# ATmega328.net
KiCad netlist of a schematic drawn in EAGLE
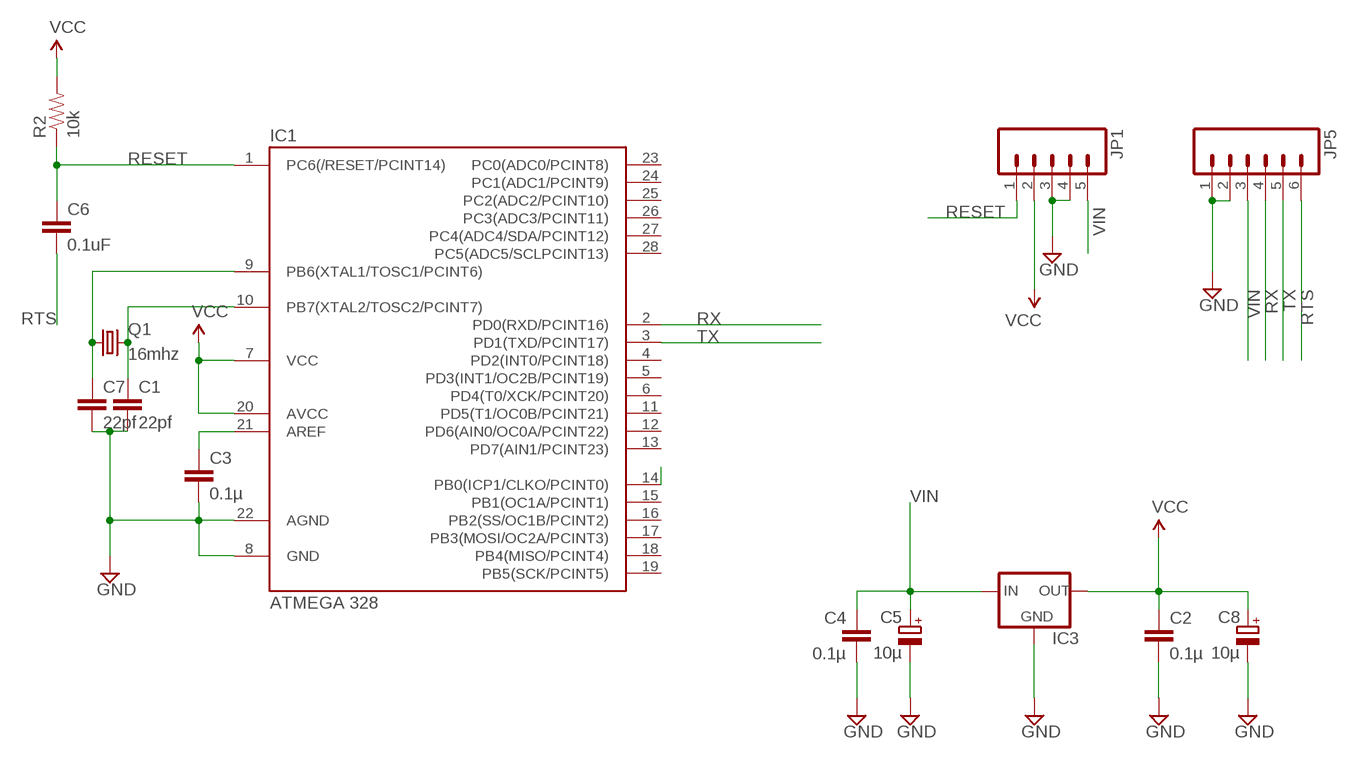
[diagram p0: schematic, sheet 1]

(export (version "E")
  (design (tool "Eeschema 10.0.6"))
  (components
    (comp (ref "C1")
      (value "22pf")
      (footprint "eagle-import:C025-024X044")
      (libsource (lib "eagle-import") (part "C-EU025-024X044"))
    )
    (comp (ref "C2")
      (value "0.1µ")
      (footprint "eagle-import:C025-024X044")
      (libsource (lib "eagle-import") (part "C-EU025-024X044"))
    )
    (comp (ref "C3")
      (value "0.1µ")
      (footprint "eagle-import:C025-024X044")
      (libsource (lib "eagle-import") (part "C-EU025-024X044"))
    )
    (comp (ref "C4")
      (value "0.1µ")
      (footprint "eagle-import:C025-024X044")
      (libsource (lib "eagle-import") (part "C-EU025-024X044"))
    )
    (comp (ref "C5")
      (value "10µ")
      (footprint "eagle-import:E1,8-4")
      (libsource (lib "eagle-import") (part "CPOL-EUE1.8-4"))
    )
    (comp (ref "C6")
      (value "0.1uF")
      (footprint "eagle-import:CAP-PTH-5MM")
      (libsource (lib "eagle-import") (part "CAPPTH1"))
    )
    (comp (ref "C7")
      (value "22pf")
      (footprint "eagle-import:C025-024X044")
      (libsource (lib "eagle-import") (part "C-EU025-024X044"))
    )
    (comp (ref "C8")
      (value "10µ")
      (footprint "eagle-import:E1,8-4")
      (libsource (lib "eagle-import") (part "CPOL-EUE1.8-4"))
    )
    (comp (ref "IC1")
      (value "ATMEGA 328")
      (footprint "eagle-import:DIL28-3")
      (libsource (lib "eagle-import") (part "ATMEGA48/88/168-PU"))
    )
    (comp (ref "IC3")
      (value "V_REG_78XXSIDE")
      (footprint "eagle-import:78XXL")
      (libsource (lib "eagle-import") (part "V_REG_78XXSIDE"))
    )
    (comp (ref "JP1")
      (value "M05PTH_LONGPADS")
      (footprint "eagle-import:1X05_LONGPADS")
      (libsource (lib "eagle-import") (part "M05PTH_LONGPADS"))
    )
    (comp (ref "JP5")
      (value "M06NO_SILK")
      (footprint "eagle-import:1X06_NO_SILK")
      (libsource (lib "eagle-import") (part "M06NO_SILK"))
    )
    (comp (ref "Q1")
      (value "16mhz")
      (footprint "eagle-import:HC49_S")
      (libsource (lib "eagle-import") (part "CRYSTALHC49S"))
    )
    (comp (ref "R2")
      (value "10k")
      (footprint "eagle-import:1_6W-RES")
      (libsource (lib "eagle-import") (part "RESISTORPTH-1/6W"))
    )
  )
  (nets
    (net (code "1") (name "/RESET") (class "Default")
      (node (ref "C6") (pin "1") (pinfunction "1_1") (pintype "passive"))
      (node (ref "IC1") (pin "1") (pinfunction "PC6(/RESET/PCINT14)_1") (pintype "bidirectional"))
      (node (ref "JP1") (pin "1") (pinfunction "1_1") (pintype "passive"))
      (node (ref "R2") (pin "1") (pinfunction "1_1") (pintype "passive"))
    )
    (net (code "2") (name "/RTS") (class "Default")
      (node (ref "C6") (pin "2") (pinfunction "2_2") (pintype "passive"))
      (node (ref "JP5") (pin "6") (pinfunction "6_6") (pintype "passive"))
    )
    (net (code "3") (name "/RX") (class "Default")
      (node (ref "IC1") (pin "2") (pinfunction "PD0(RXD/PCINT16)_2") (pintype "bidirectional"))
      (node (ref "JP5") (pin "4") (pinfunction "4_4") (pintype "passive"))
    )
    (net (code "4") (name "/TX") (class "Default")
      (node (ref "IC1") (pin "3") (pinfunction "PD1(TXD/PCINT17)_3") (pintype "bidirectional"))
      (node (ref "JP5") (pin "5") (pinfunction "5_5") (pintype "passive"))
    )
    (net (code "5") (name "/VIN") (class "Default")
      (node (ref "C4") (pin "1") (pinfunction "1_1") (pintype "passive"))
      (node (ref "C5") (pin "+") (pinfunction "+_+") (pintype "passive"))
      (node (ref "IC3") (pin "IN") (pinfunction "IN_IN") (pintype "input"))
      (node (ref "JP1") (pin "5") (pinfunction "5_5") (pintype "passive"))
      (node (ref "JP5") (pin "3") (pinfunction "3_3") (pintype "passive"))
    )
    (net (code "6") (name "GND") (class "Default")
      (node (ref "C1") (pin "2") (pinfunction "2_2") (pintype "passive"))
      (node (ref "C2") (pin "2") (pinfunction "2_2") (pintype "passive"))
      (node (ref "C3") (pin "2") (pinfunction "2_2") (pintype "passive"))
      (node (ref "C4") (pin "2") (pinfunction "2_2") (pintype "passive"))
      (node (ref "C5") (pin "-") (pinfunction "-_-") (pintype "passive"))
      (node (ref "C7") (pin "2") (pinfunction "2_2") (pintype "passive"))
      (node (ref "C8") (pin "-") (pinfunction "-_-") (pintype "passive"))
      (node (ref "IC1") (pin "22") (pinfunction "AGND_22") (pintype "power_in"))
      (node (ref "IC1") (pin "8") (pinfunction "GND_8") (pintype "power_in"))
      (node (ref "IC3") (pin "GND") (pinfunction "GND_GND") (pintype "input"))
      (node (ref "JP1") (pin "3") (pinfunction "3_3") (pintype "passive"))
      (node (ref "JP1") (pin "4") (pinfunction "4_4") (pintype "passive"))
      (node (ref "JP5") (pin "1") (pinfunction "1_1") (pintype "passive"))
      (node (ref "JP5") (pin "2") (pinfunction "2_2") (pintype "passive"))
    )
    (net (code "7") (name "Net-(IC1-AREF)") (class "Default")
      (node (ref "C3") (pin "1") (pinfunction "1_1") (pintype "passive"))
      (node (ref "IC1") (pin "21") (pinfunction "AREF_21") (pintype "passive"))
    )
    (net (code "8") (name "Net-(IC1-PB6(XTAL1{slash}TOSC1{slash}PCINT6))") (class "Default")
      (node (ref "C7") (pin "1") (pinfunction "1_1") (pintype "passive"))
      (node (ref "IC1") (pin "9") (pinfunction "PB6(XTAL1/TOSC1/PCINT6)_9") (pintype "bidirectional"))
      (node (ref "Q1") (pin "1") (pinfunction "1_1") (pintype "passive"))
    )
    (net (code "9") (name "Net-(IC1-PB7(XTAL2{slash}TOSC2{slash}PCINT7))") (class "Default")
      (node (ref "C1") (pin "1") (pinfunction "1_1") (pintype "passive"))
      (node (ref "IC1") (pin "10") (pinfunction "PB7(XTAL2/TOSC2/PCINT7)_10") (pintype "bidirectional"))
      (node (ref "Q1") (pin "2") (pinfunction "2_2") (pintype "passive"))
    )
    (net (code "10") (name "VCC") (class "Default")
      (node (ref "C2") (pin "1") (pinfunction "1_1") (pintype "passive"))
      (node (ref "C8") (pin "+") (pinfunction "+_+") (pintype "passive"))
      (node (ref "IC1") (pin "20") (pinfunction "AVCC_20") (pintype "passive"))
      (node (ref "IC1") (pin "7") (pinfunction "VCC_7") (pintype "power_in"))
      (node (ref "IC3") (pin "OUT") (pinfunction "OUT_OUT") (pintype "output"))
      (node (ref "JP1") (pin "2") (pinfunction "2_2") (pintype "passive"))
      (node (ref "R2") (pin "2") (pinfunction "2_2") (pintype "passive"))
    )
    (net (code "11") (name "unconnected-(IC1-PB0(ICP1{slash}CLKO{slash}PCINT0)-Pad14)") (class "Default")
      (node (ref "IC1") (pin "14") (pinfunction "PB0(ICP1/CLKO/PCINT0)_14") (pintype "bidirectional"))
    )
    (net (code "12") (name "unconnected-(IC1-PB1(OC1A{slash}PCINT1)-Pad15)") (class "Default")
      (node (ref "IC1") (pin "15") (pinfunction "PB1(OC1A/PCINT1)_15") (pintype "bidirectional"))
    )
    (net (code "13") (name "unconnected-(IC1-PB2(SS{slash}OC1B{slash}PCINT2)-Pad16)") (class "Default")
      (node (ref "IC1") (pin "16") (pinfunction "PB2(SS/OC1B/PCINT2)_16") (pintype "bidirectional"))
    )
    (net (code "14") (name "unconnected-(IC1-PB3(MOSI{slash}OC2A{slash}PCINT3)-Pad17)") (class "Default")
      (node (ref "IC1") (pin "17") (pinfunction "PB3(MOSI/OC2A/PCINT3)_17") (pintype "bidirectional"))
    )
    (net (code "15") (name "unconnected-(IC1-PB4(MISO{slash}PCINT4)-Pad18)") (class "Default")
      (node (ref "IC1") (pin "18") (pinfunction "PB4(MISO/PCINT4)_18") (pintype "bidirectional"))
    )
    (net (code "16") (name "unconnected-(IC1-PB5(SCK{slash}PCINT5)-Pad19)") (class "Default")
      (node (ref "IC1") (pin "19") (pinfunction "PB5(SCK/PCINT5)_19") (pintype "bidirectional"))
    )
    (net (code "17") (name "unconnected-(IC1-PC0(ADC0{slash}PCINT8)-Pad23)") (class "Default")
      (node (ref "IC1") (pin "23") (pinfunction "PC0(ADC0/PCINT8)_23") (pintype "bidirectional"))
    )
    (net (code "18") (name "unconnected-(IC1-PC1(ADC1{slash}PCINT9)-Pad24)") (class "Default")
      (node (ref "IC1") (pin "24") (pinfunction "PC1(ADC1/PCINT9)_24") (pintype "bidirectional"))
    )
    (net (code "19") (name "unconnected-(IC1-PC2(ADC2{slash}PCINT10)-Pad25)") (class "Default")
      (node (ref "IC1") (pin "25") (pinfunction "PC2(ADC2/PCINT10)_25") (pintype "bidirectional"))
    )
    (net (code "20") (name "unconnected-(IC1-PC3(ADC3{slash}PCINT11)-Pad26)") (class "Default")
      (node (ref "IC1") (pin "26") (pinfunction "PC3(ADC3/PCINT11)_26") (pintype "bidirectional"))
    )
    (net (code "21") (name "unconnected-(IC1-PC4(ADC4{slash}SDA{slash}PCINT12)-Pad27)") (class "Default")
      (node (ref "IC1") (pin "27") (pinfunction "PC4(ADC4/SDA/PCINT12)_27") (pintype "bidirectional"))
    )
    (net (code "22") (name "unconnected-(IC1-PC5(ADC5{slash}SCLPCINT13)-Pad28)") (class "Default")
      (node (ref "IC1") (pin "28") (pinfunction "PC5(ADC5/SCLPCINT13)_28") (pintype "bidirectional"))
    )
    (net (code "23") (name "unconnected-(IC1-PD2(INT0{slash}PCINT18)-Pad4)") (class "Default")
      (node (ref "IC1") (pin "4") (pinfunction "PD2(INT0/PCINT18)_4") (pintype "bidirectional"))
    )
    (net (code "24") (name "unconnected-(IC1-PD3(INT1{slash}OC2B{slash}PCINT19)-Pad5)") (class "Default")
      (node (ref "IC1") (pin "5") (pinfunction "PD3(INT1/OC2B/PCINT19)_5") (pintype "bidirectional"))
    )
    (net (code "25") (name "unconnected-(IC1-PD4(T0{slash}XCK{slash}PCINT20)-Pad6)") (class "Default")
      (node (ref "IC1") (pin "6") (pinfunction "PD4(T0/XCK/PCINT20)_6") (pintype "bidirectional"))
    )
    (net (code "26") (name "unconnected-(IC1-PD5(T1{slash}OC0B{slash}PCINT21)-Pad11)") (class "Default")
      (node (ref "IC1") (pin "11") (pinfunction "PD5(T1/OC0B/PCINT21)_11") (pintype "bidirectional"))
    )
    (net (code "27") (name "unconnected-(IC1-PD6(AIN0{slash}OC0A{slash}PCINT22)-Pad12)") (class "Default")
      (node (ref "IC1") (pin "12") (pinfunction "PD6(AIN0/OC0A/PCINT22)_12") (pintype "bidirectional"))
    )
    (net (code "28") (name "unconnected-(IC1-PD7(AIN1{slash}PCINT23)-Pad13)") (class "Default")
      (node (ref "IC1") (pin "13") (pinfunction "PD7(AIN1/PCINT23)_13") (pintype "bidirectional"))
    )
  )
)
